# Leds.net
KiCad netlist of a schematic drawn in Altium Designer
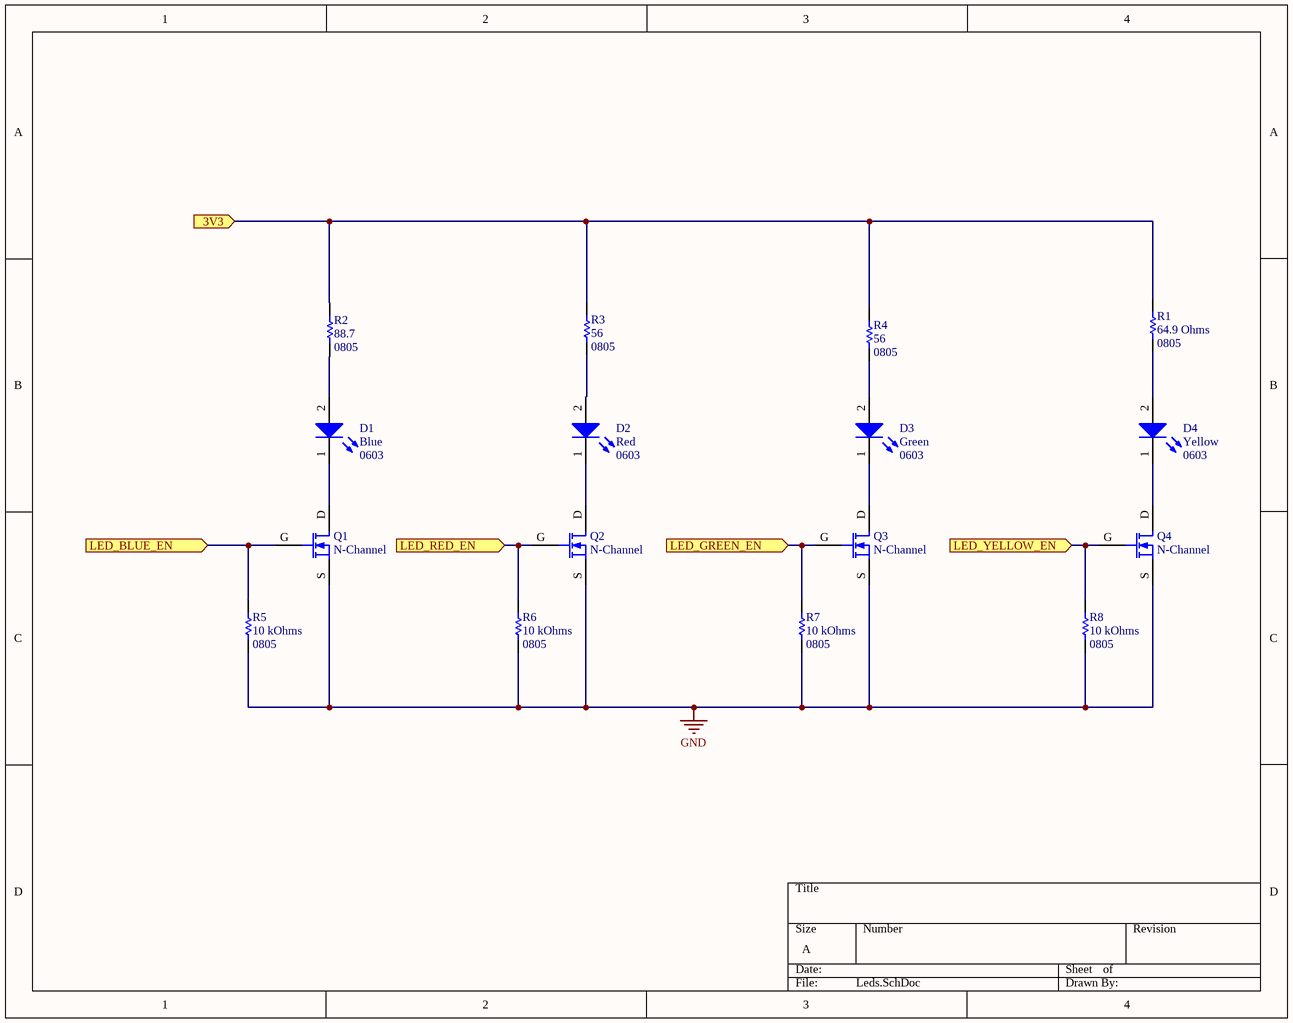
[diagram p0: Leds.SchDoc]

(export (version "E")
  (design (tool "Eeschema 10.0.6"))
  (components
    (comp (ref "D1")
      (value "SMLE12BC7TT86")
      (footprint "SMLE12BC7TT86")
      (description "LED BLUE CLEAR 0603 SMD")
      (fields (field (name "COLOR") "Blue") (field (name "PACKAGE / CASE") "0603"))
      (libsource (lib "LEDs") (part "SMLE12BC7TT86"))
    )
    (comp (ref "D2")
      (value "SML-D12U8WT86")
      (footprint "SML-D12U8WT86")
      (description "LED RED DIFFUSED 0603 SMD")
      (fields (field (name "COLOR") "Red") (field (name "PACKAGE / CASE") "0603"))
      (libsource (lib "LEDs") (part "SML-D12U8WT86"))
    )
    (comp (ref "D3")
      (value "SML-D12M8WT86")
      (footprint "SML-D12M8WT86")
      (description "LED GREEN DIFFUSED 0603 SMD")
      (fields (field (name "COLOR") "Green") (field (name "PACKAGE / CASE") "0603"))
      (libsource (lib "LEDs") (part "SML-D12M8WT86"))
    )
    (comp (ref "D4")
      (value "SML-511WWT86")
      (footprint "SML-511WWT86")
      (description "LED YELLOW DIFFUSED 0603 SMD")
      (fields (field (name "COLOUR") "Yellow") (field (name "PACKAGE / CASE") "0603"))
      (libsource (lib "LEDs") (part "SML-511WWT86"))
    )
    (comp (ref "Q1")
      (value "2N7002P,215")
      (footprint "2N7002P,215")
      (description "MOSFET N-CH 60V 0.36A SOT-23")
      (fields (field (name "FET TYPE") "N-Channel"))
      (libsource (lib "Transistors") (part "2N7002P,215"))
    )
    (comp (ref "Q2")
      (value "2N7002P,215")
      (footprint "2N7002P,215")
      (description "MOSFET N-CH 60V 0.36A SOT-23")
      (fields (field (name "FET TYPE") "N-Channel"))
      (libsource (lib "Transistors") (part "2N7002P,215"))
    )
    (comp (ref "Q3")
      (value "2N7002P,215")
      (footprint "2N7002P,215")
      (description "MOSFET N-CH 60V 0.36A SOT-23")
      (fields (field (name "FET TYPE") "N-Channel"))
      (libsource (lib "Transistors") (part "2N7002P,215"))
    )
    (comp (ref "Q4")
      (value "2N7002P,215")
      (footprint "2N7002P,215")
      (description "MOSFET N-CH 60V 0.36A SOT-23")
      (fields (field (name "FET TYPE") "N-Channel"))
      (libsource (lib "Transistors") (part "2N7002P,215"))
    )
    (comp (ref "R1")
      (value "ERJ-6ENF64R9V")
      (footprint "RES0805")
      (description "RES SMD 64.9 OHM 1% 1/8W 0805")
      (fields
        (field (name "TOLERANCE") "±1%")
        (field (name "RESISTANCE") "64.9 Ohms")
        (field (name "PACKAGE / CASE") "0805")
      )
      (libsource (lib "Resistors") (part "ERJ-6ENF64R9V"))
    )
    (comp (ref "R2")
      (value "CRCW080588R7FKEA")
      (footprint "RES0805")
      (description "RES SMD 88.7 OHM 1% 1/8W 0805")
      (fields
        (field (name "TOLERANCE") "±1%")
        (field (name "RESISTANCE") "88.7")
        (field (name "PACKAGE / CASE") "0805")
      )
      (libsource (lib "Resistors") (part "CRCW080588R7FKEA"))
    )
    (comp (ref "R3")
      (value "RMCF0805JT56R0")
      (footprint "RES0805")
      (description "RES SMD 56 OHM 5% 1/8W 0805")
      (fields (field (name "RESISTANCE (OHMS)") "56") (field (name "PACKAGE / CASE") "0805"))
      (libsource (lib "Resistors") (part "RMCF0805JT56R0"))
    )
    (comp (ref "R4")
      (value "RMCF0805JT56R0")
      (footprint "RES0805")
      (description "RES SMD 56 OHM 5% 1/8W 0805")
      (fields (field (name "RESISTANCE (OHMS)") "56") (field (name "PACKAGE / CASE") "0805"))
      (libsource (lib "Resistors") (part "RMCF0805JT56R0"))
    )
    (comp (ref "R5")
      (value "RC0805FR-0710KL")
      (footprint "RES0805")
      (description "RES SMD 10K OHM 1% 1/8W 0805")
      (fields
        (field (name "MANUFACTURER") "Yageo")
        (field (name "TOLERANCE") "±1%")
        (field (name "RESISTANCE") "10 kOhms")
        (field (name "PACKAGE / CASE") "0805")
      )
      (libsource (lib "Resistors") (part "RC0805FR-0710KL"))
    )
    (comp (ref "R6")
      (value "RMCF0805FT10K0")
      (footprint "RES0805")
      (description "RES SMD 10K OHM 1% 1/8W 0805")
      (fields
        (field (name "TOLERANCE") "±1%")
        (field (name "RESISTANCE") "10 kOhms")
        (field (name "PACKAGE / CASE") "0805")
      )
      (libsource (lib "Resistors") (part "RMCF0805FT10K0"))
    )
    (comp (ref "R7")
      (value "RMCF0805FT10K0")
      (footprint "RES0805")
      (description "RES SMD 10K OHM 1% 1/8W 0805")
      (fields
        (field (name "TOLERANCE") "±1%")
        (field (name "RESISTANCE") "10 kOhms")
        (field (name "PACKAGE / CASE") "0805")
      )
      (libsource (lib "Resistors") (part "RMCF0805FT10K0"))
    )
    (comp (ref "R8")
      (value "RMCF0805FT10K0")
      (footprint "RES0805")
      (description "RES SMD 10K OHM 1% 1/8W 0805")
      (fields
        (field (name "TOLERANCE") "±1%")
        (field (name "RESISTANCE") "10 kOhms")
        (field (name "PACKAGE / CASE") "0805")
      )
      (libsource (lib "Resistors") (part "RMCF0805FT10K0"))
    )
  )
  (nets
    (net (code "1") (name "/3V3") (class "Default")
      (node (ref "R1") (pin "2") (pinfunction "2_2") (pintype "passive"))
      (node (ref "R2") (pin "2") (pinfunction "2_2") (pintype "passive"))
      (node (ref "R3") (pin "2") (pinfunction "2_2") (pintype "passive"))
      (node (ref "R4") (pin "2") (pinfunction "2_2") (pintype "passive"))
    )
    (net (code "2") (name "/LED_BLUE_EN") (class "Default")
      (node (ref "Q1") (pin "G") (pinfunction "G_G") (pintype "passive"))
      (node (ref "R5") (pin "2") (pinfunction "2_2") (pintype "passive"))
    )
    (net (code "3") (name "/LED_GREEN_EN") (class "Default")
      (node (ref "Q3") (pin "G") (pinfunction "G_G") (pintype "passive"))
      (node (ref "R7") (pin "2") (pinfunction "2_2") (pintype "passive"))
    )
    (net (code "4") (name "/LED_RED_EN") (class "Default")
      (node (ref "Q2") (pin "G") (pinfunction "G_G") (pintype "passive"))
      (node (ref "R6") (pin "2") (pinfunction "2_2") (pintype "passive"))
    )
    (net (code "5") (name "/LED_YELLOW_EN") (class "Default")
      (node (ref "Q4") (pin "G") (pinfunction "G_G") (pintype "passive"))
      (node (ref "R8") (pin "2") (pinfunction "2_2") (pintype "passive"))
    )
    (net (code "6") (name "GND") (class "Default")
      (node (ref "Q1") (pin "S") (pinfunction "S_S") (pintype "passive"))
      (node (ref "Q2") (pin "S") (pinfunction "S_S") (pintype "passive"))
      (node (ref "Q3") (pin "S") (pinfunction "S_S") (pintype "passive"))
      (node (ref "Q4") (pin "S") (pinfunction "S_S") (pintype "passive"))
      (node (ref "R5") (pin "1") (pinfunction "1_1") (pintype "passive"))
      (node (ref "R6") (pin "1") (pinfunction "1_1") (pintype "passive"))
      (node (ref "R7") (pin "1") (pinfunction "1_1") (pintype "passive"))
      (node (ref "R8") (pin "1") (pinfunction "1_1") (pintype "passive"))
    )
    (net (code "7") (name "Net-(D1-A)") (class "Default")
      (node (ref "D1") (pin "2") (pinfunction "A_2") (pintype "passive"))
      (node (ref "R2") (pin "1") (pinfunction "1_1") (pintype "passive"))
    )
    (net (code "8") (name "Net-(D1-K)") (class "Default")
      (node (ref "D1") (pin "1") (pinfunction "K_1") (pintype "passive"))
      (node (ref "Q1") (pin "D") (pinfunction "D_D") (pintype "passive"))
    )
    (net (code "9") (name "Net-(D2-A)") (class "Default")
      (node (ref "D2") (pin "2") (pinfunction "A_2") (pintype "passive"))
      (node (ref "R3") (pin "1") (pinfunction "1_1") (pintype "passive"))
    )
    (net (code "10") (name "Net-(D2-K)") (class "Default")
      (node (ref "D2") (pin "1") (pinfunction "K_1") (pintype "passive"))
      (node (ref "Q2") (pin "D") (pinfunction "D_D") (pintype "passive"))
    )
    (net (code "11") (name "Net-(D3-A)") (class "Default")
      (node (ref "D3") (pin "2") (pinfunction "A_2") (pintype "passive"))
      (node (ref "R4") (pin "1") (pinfunction "1_1") (pintype "passive"))
    )
    (net (code "12") (name "Net-(D3-K)") (class "Default")
      (node (ref "D3") (pin "1") (pinfunction "K_1") (pintype "passive"))
      (node (ref "Q3") (pin "D") (pinfunction "D_D") (pintype "passive"))
    )
    (net (code "13") (name "Net-(D4-A)") (class "Default")
      (node (ref "D4") (pin "2") (pinfunction "A_2") (pintype "passive"))
      (node (ref "R1") (pin "1") (pinfunction "1_1") (pintype "passive"))
    )
    (net (code "14") (name "Net-(D4-K)") (class "Default")
      (node (ref "D4") (pin "1") (pinfunction "K_1") (pintype "passive"))
      (node (ref "Q4") (pin "D") (pinfunction "D_D") (pintype "passive"))
    )
  )
)
